# U4BNV1_Schematic.net
KiCad netlist of a schematic drawn in Altium Designer
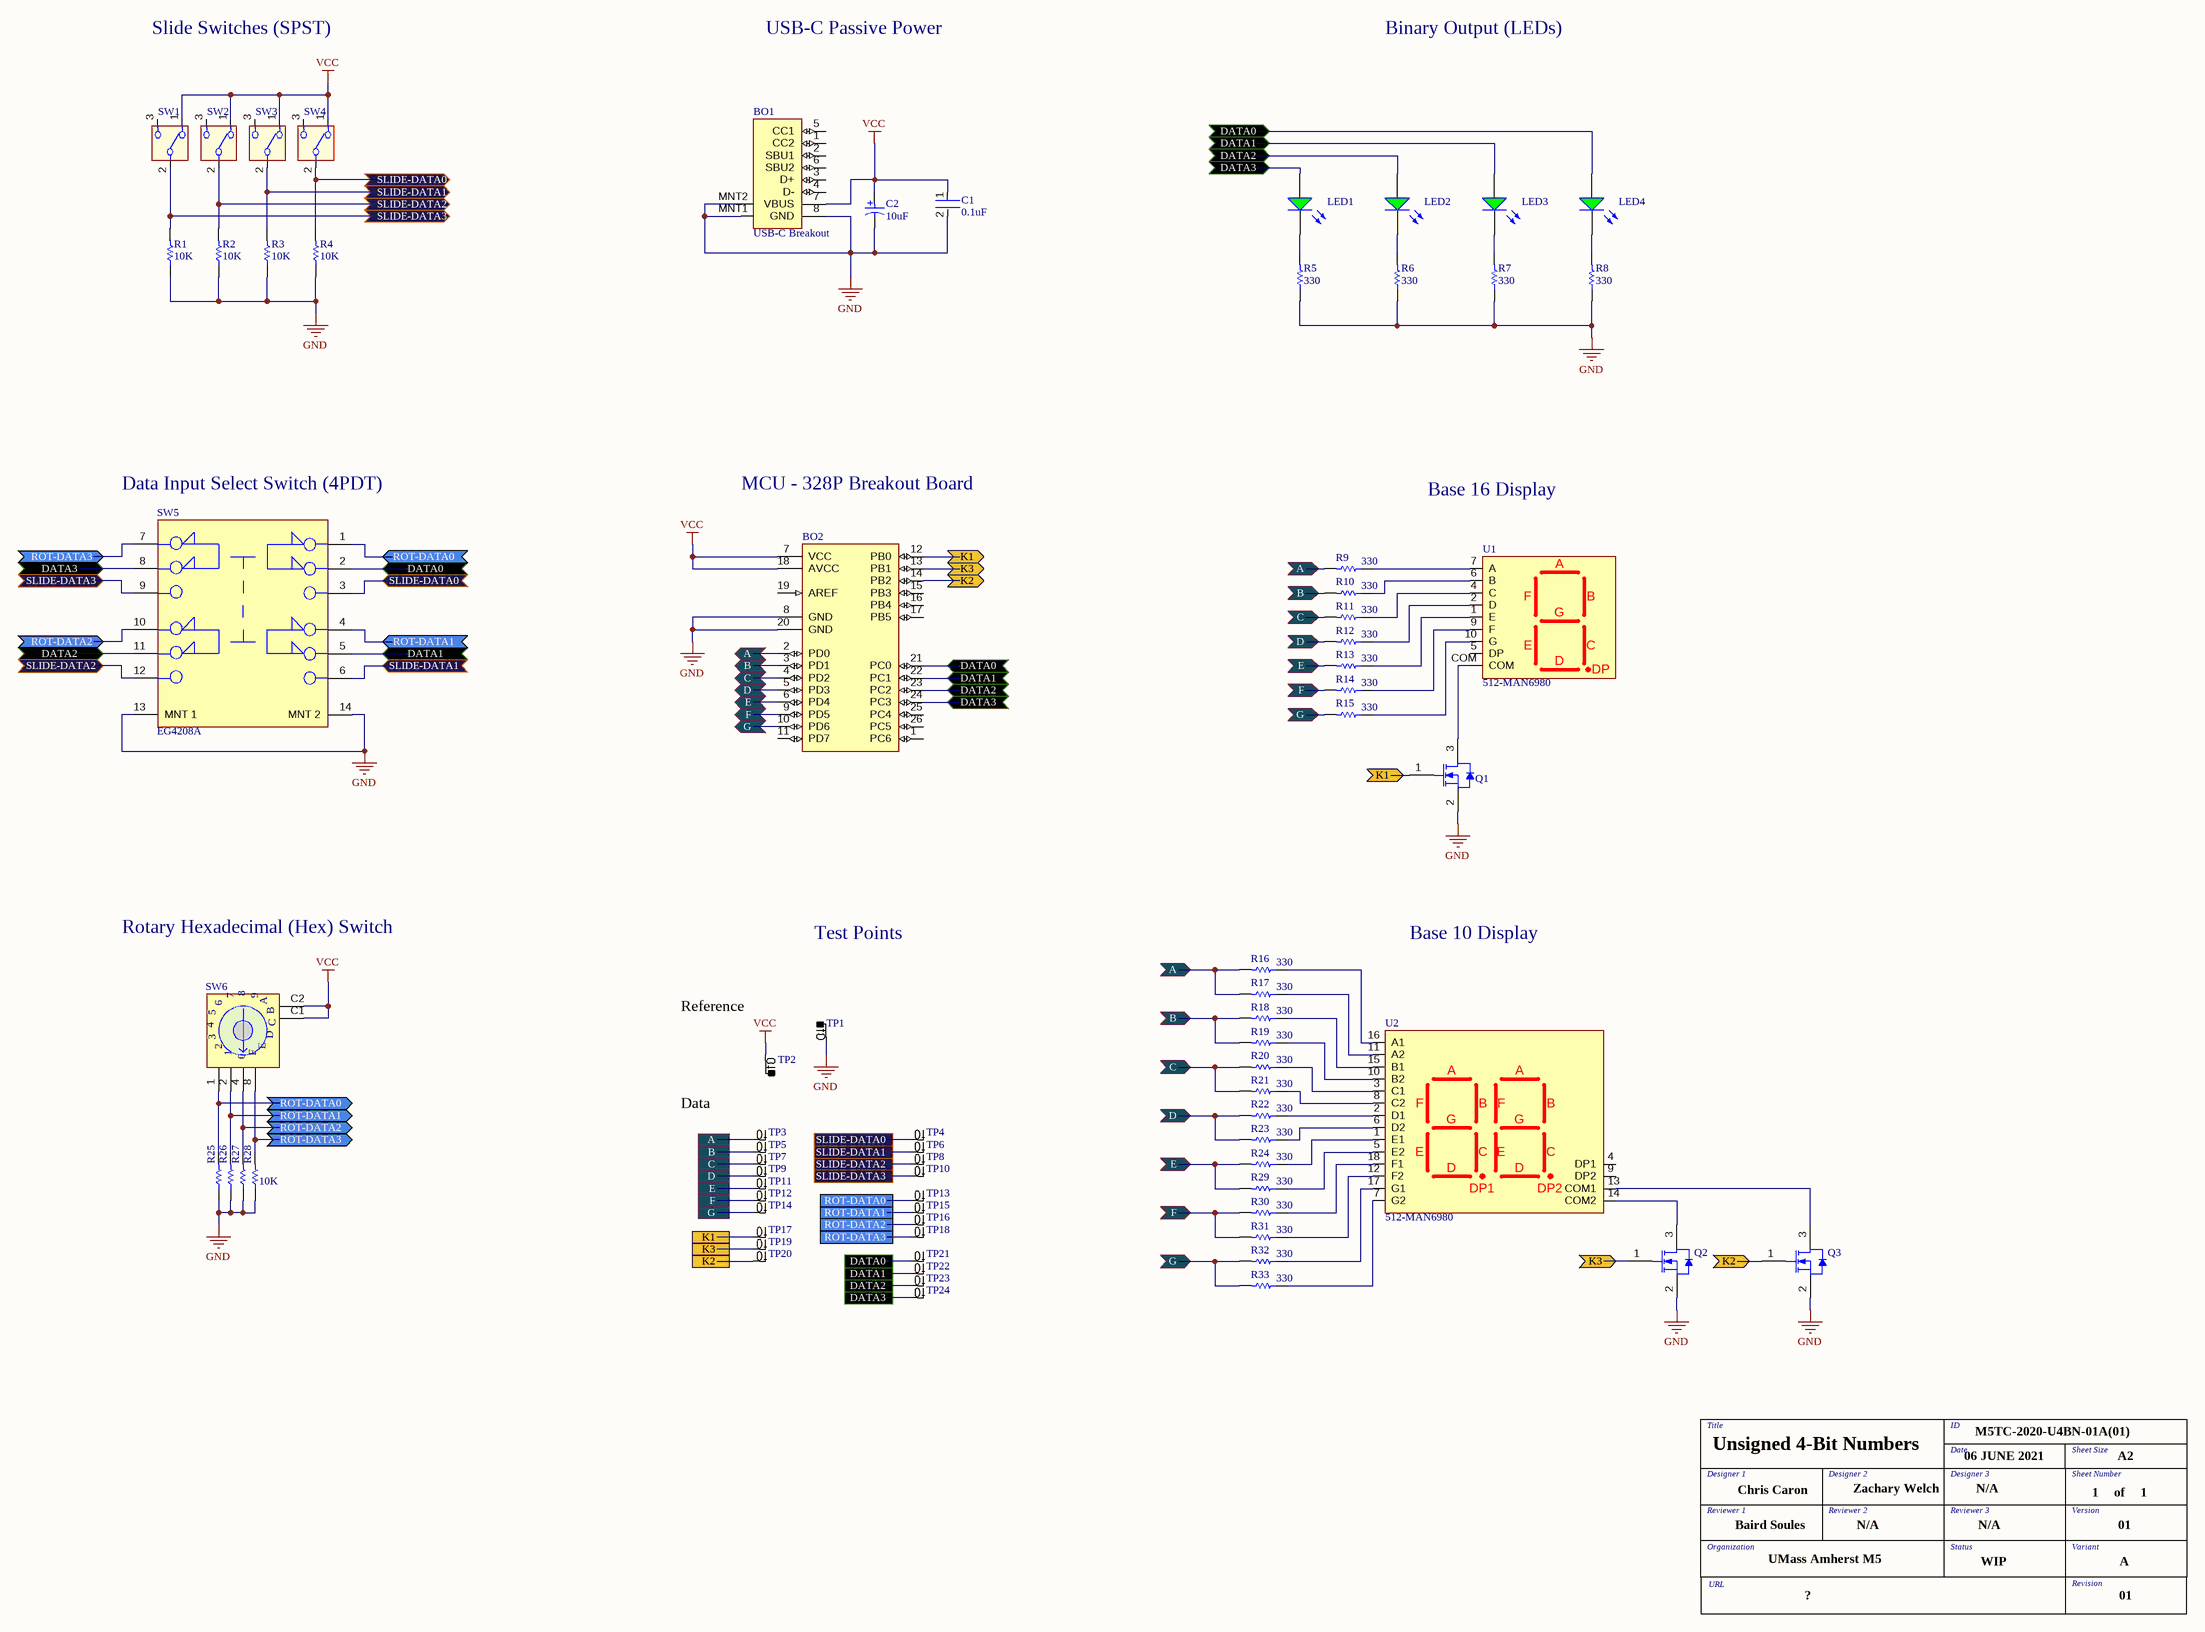
[diagram p0: U4BNV1 Schematic.SchDoc]

(export (version "E")
  (design (tool "Eeschema 10.0.6"))
  (components
    (comp (ref "BO1")
      (value "USB-C Breakout")
      (footprint "USB-C Breakout")
      (libsource (lib "U4BNV1 SchLib") (part "USB-C Breakout"))
    )
    (comp (ref "BO2")
      (value "~")
      (footprint "328P-BOB")
      (description "Custom Breakout Board for 328P-PU")
      (libsource (lib "Master Schematic Library") (part "328P-BOB"))
    )
    (comp (ref "C1")
      (value "0.1uF")
      (footprint "FP-C0603-CJ-MFG")
      (description "CAP CER 0.1UF 50V X7R 0603")
      (fields (field (name "MANUFACTURER PART NUMBER") "C0603X104K5RACTU") (field (name "VOLTAGE") "50V"))
      (libsource (lib "Altium Content Vault") (part "11868f565c42a9108669ba33697ecf6"))
    )
    (comp (ref "C2")
      (value "10uF")
      (footprint "KEMT-A-3216-18-2_M")
      (description "Capacitor, Tantalum, 10 uF, +/- 10%, 10 V, -55 to 125 degC, 2-Pin SMD (1206), RoHS, Tape and Reel")
      (fields (field (name "TOLERANCE") "±10%") (field (name "MANUFACTURER") "Kemet"))
      (libsource (lib "Altium Content Vault") (part "CAP-P-2"))
    )
    (comp (ref "LED1")
      (value "HLMP-4740")
      (footprint "AVAG-HLMP-4740")
      (description "T-1 3/4 (5 mm) Low Current LED Lamp, Green, 1.9 V, -20 to 100 degC, 2-Pin THD, RoHS, Bulk")
      (fields (field (name "MANUFACTURER") "AvagoTechnologies"))
      (libsource (lib "Altium Content Vault") (part "LED-GREEN-AK-2"))
    )
    (comp (ref "LED2")
      (value "HLMP-4740")
      (footprint "AVAG-HLMP-4740")
      (description "T-1 3/4 (5 mm) Low Current LED Lamp, Green, 1.9 V, -20 to 100 degC, 2-Pin THD, RoHS, Bulk")
      (fields (field (name "MANUFACTURER") "AvagoTechnologies"))
      (libsource (lib "Altium Content Vault") (part "LED-GREEN-AK-2"))
    )
    (comp (ref "LED3")
      (value "HLMP-4740")
      (footprint "AVAG-HLMP-4740")
      (description "T-1 3/4 (5 mm) Low Current LED Lamp, Green, 1.9 V, -20 to 100 degC, 2-Pin THD, RoHS, Bulk")
      (fields (field (name "MANUFACTURER") "AvagoTechnologies"))
      (libsource (lib "Altium Content Vault") (part "LED-GREEN-AK-2"))
    )
    (comp (ref "LED4")
      (value "HLMP-4740")
      (footprint "AVAG-HLMP-4740")
      (description "T-1 3/4 (5 mm) Low Current LED Lamp, Green, 1.9 V, -20 to 100 degC, 2-Pin THD, RoHS, Bulk")
      (fields (field (name "MANUFACTURER") "AvagoTechnologies"))
      (libsource (lib "Altium Content Vault") (part "LED-GREEN-AK-2"))
    )
    (comp (ref "Q1")
      (value "FDN337N")
      (footprint "FAIR-SSOT3L-3_V")
      (fields (field (name "MANUFACTURER") "Fairchild Semiconductor"))
      (libsource (lib "Altium Content Vault") (part "NEMOS-GSD-3"))
    )
    (comp (ref "Q2")
      (value "FDN337N")
      (footprint "FAIR-SSOT3L-3_V")
      (fields (field (name "MANUFACTURER") "Fairchild Semiconductor"))
      (libsource (lib "Altium Content Vault") (part "NEMOS-GSD-3"))
    )
    (comp (ref "Q3")
      (value "FDN337N")
      (footprint "FAIR-SSOT3L-3_V")
      (fields (field (name "MANUFACTURER") "Fairchild Semiconductor"))
      (libsource (lib "Altium Content Vault") (part "NEMOS-GSD-3"))
    )
    (comp (ref "R1")
      (value "10K")
      (footprint "RESC1608X55X30LL10T20_B")
      (description "Chip Resistor, 10 KOhm, +/- 1%, 0.1 W, -55 to 125 degC, 0603 (1608 Metric), RoHS, Tape and Reel")
      (fields (field (name "MANUFACTURER") "TE Connectivity") (field (name "TOLERANCE") "1%"))
      (libsource (lib "Altium Content Vault") (part "RES-2"))
    )
    (comp (ref "R2")
      (value "10K")
      (footprint "RESC1608X55X30LL10T20_B")
      (description "Chip Resistor, 10 KOhm, +/- 1%, 0.1 W, -55 to 125 degC, 0603 (1608 Metric), RoHS, Tape and Reel")
      (fields (field (name "MANUFACTURER") "TE Connectivity") (field (name "TOLERANCE") "1%"))
      (libsource (lib "Altium Content Vault") (part "RES-2"))
    )
    (comp (ref "R3")
      (value "10K")
      (footprint "RESC1608X55X30LL10T20_B")
      (description "Chip Resistor, 10 KOhm, +/- 1%, 0.1 W, -55 to 125 degC, 0603 (1608 Metric), RoHS, Tape and Reel")
      (fields (field (name "MANUFACTURER") "TE Connectivity") (field (name "TOLERANCE") "1%"))
      (libsource (lib "Altium Content Vault") (part "RES-2"))
    )
    (comp (ref "R4")
      (value "10K")
      (footprint "RESC1608X55X30LL10T20_B")
      (description "Chip Resistor, 10 KOhm, +/- 1%, 0.1 W, -55 to 125 degC, 0603 (1608 Metric), RoHS, Tape and Reel")
      (fields (field (name "MANUFACTURER") "TE Connectivity") (field (name "TOLERANCE") "1%"))
      (libsource (lib "Altium Content Vault") (part "RES-2"))
    )
    (comp (ref "R5")
      (value "330")
      (footprint "RESC1608X55X25NL10T15")
      (description "Chip Resistor, 330 Ohm, +/- 1%, 0.1 W, -55 to 155 degC, 0603 (1608 Metric), RoHS, Tape and Reel")
      (fields (field (name "TOLERANCE") "10%"))
      (libsource (lib "Altium Content Vault") (part "RES-2"))
    )
    (comp (ref "R6")
      (value "330")
      (footprint "RESC1608X55X25NL10T15")
      (description "Chip Resistor, 330 Ohm, +/- 1%, 0.1 W, -55 to 155 degC, 0603 (1608 Metric), RoHS, Tape and Reel")
      (fields (field (name "TOLERANCE") "10%"))
      (libsource (lib "Altium Content Vault") (part "RES-2"))
    )
    (comp (ref "R7")
      (value "330")
      (footprint "RESC1608X55X25NL10T15")
      (description "Chip Resistor, 330 Ohm, +/- 1%, 0.1 W, -55 to 155 degC, 0603 (1608 Metric), RoHS, Tape and Reel")
      (fields (field (name "TOLERANCE") "10%"))
      (libsource (lib "Altium Content Vault") (part "RES-2"))
    )
    (comp (ref "R8")
      (value "330")
      (footprint "RESC1608X55X25NL10T15")
      (description "Chip Resistor, 330 Ohm, +/- 1%, 0.1 W, -55 to 155 degC, 0603 (1608 Metric), RoHS, Tape and Reel")
      (fields (field (name "TOLERANCE") "10%"))
      (libsource (lib "Altium Content Vault") (part "RES-2"))
    )
    (comp (ref "R9")
      (value "330")
      (footprint "RESC1608X55X25NL10T15")
      (description "Chip Resistor, 330 Ohm, +/- 1%, 0.1 W, -55 to 155 degC, 0603 (1608 Metric), RoHS, Tape and Reel")
      (fields (field (name "TOLERANCE") "10%"))
      (libsource (lib "Altium Content Vault") (part "RES-2"))
    )
    (comp (ref "R10")
      (value "330")
      (footprint "RESC1608X55X25NL10T15")
      (description "Chip Resistor, 330 Ohm, +/- 1%, 0.1 W, -55 to 155 degC, 0603 (1608 Metric), RoHS, Tape and Reel")
      (fields (field (name "TOLERANCE") "10%"))
      (libsource (lib "Altium Content Vault") (part "RES-2"))
    )
    (comp (ref "R11")
      (value "330")
      (footprint "RESC1608X55X25NL10T15")
      (description "Chip Resistor, 330 Ohm, +/- 1%, 0.1 W, -55 to 155 degC, 0603 (1608 Metric), RoHS, Tape and Reel")
      (fields (field (name "TOLERANCE") "10%"))
      (libsource (lib "Altium Content Vault") (part "RES-2"))
    )
    (comp (ref "R12")
      (value "330")
      (footprint "RESC1608X55X25NL10T15")
      (description "Chip Resistor, 330 Ohm, +/- 1%, 0.1 W, -55 to 155 degC, 0603 (1608 Metric), RoHS, Tape and Reel")
      (fields (field (name "TOLERANCE") "10%"))
      (libsource (lib "Altium Content Vault") (part "RES-2"))
    )
    (comp (ref "R13")
      (value "330")
      (footprint "RESC1608X55X25NL10T15")
      (description "Chip Resistor, 330 Ohm, +/- 1%, 0.1 W, -55 to 155 degC, 0603 (1608 Metric), RoHS, Tape and Reel")
      (fields (field (name "TOLERANCE") "10%"))
      (libsource (lib "Altium Content Vault") (part "RES-2"))
    )
    (comp (ref "R14")
      (value "330")
      (footprint "RESC1608X55X25NL10T15")
      (description "Chip Resistor, 330 Ohm, +/- 1%, 0.1 W, -55 to 155 degC, 0603 (1608 Metric), RoHS, Tape and Reel")
      (fields (field (name "TOLERANCE") "10%"))
      (libsource (lib "Altium Content Vault") (part "RES-2"))
    )
    (comp (ref "R15")
      (value "330")
      (footprint "RESC1608X55X25NL10T15")
      (description "Chip Resistor, 330 Ohm, +/- 1%, 0.1 W, -55 to 155 degC, 0603 (1608 Metric), RoHS, Tape and Reel")
      (fields (field (name "TOLERANCE") "10%"))
      (libsource (lib "Altium Content Vault") (part "RES-2"))
    )
    (comp (ref "R16")
      (value "330")
      (footprint "RESC1608X55X25NL10T15")
      (description "Chip Resistor, 330 Ohm, +/- 1%, 0.1 W, -55 to 155 degC, 0603 (1608 Metric), RoHS, Tape and Reel")
      (fields (field (name "TOLERANCE") "10%"))
      (libsource (lib "Altium Content Vault") (part "RES-2"))
    )
    (comp (ref "R17")
      (value "330")
      (footprint "RESC1608X55X25NL10T15")
      (description "Chip Resistor, 330 Ohm, +/- 1%, 0.1 W, -55 to 155 degC, 0603 (1608 Metric), RoHS, Tape and Reel")
      (fields (field (name "TOLERANCE") "10%"))
      (libsource (lib "Altium Content Vault") (part "RES-2"))
    )
    (comp (ref "R18")
      (value "330")
      (footprint "RESC1608X55X25NL10T15")
      (description "Chip Resistor, 330 Ohm, +/- 1%, 0.1 W, -55 to 155 degC, 0603 (1608 Metric), RoHS, Tape and Reel")
      (fields (field (name "TOLERANCE") "10%"))
      (libsource (lib "Altium Content Vault") (part "RES-2"))
    )
    (comp (ref "R19")
      (value "330")
      (footprint "RESC1608X55X25NL10T15")
      (description "Chip Resistor, 330 Ohm, +/- 1%, 0.1 W, -55 to 155 degC, 0603 (1608 Metric), RoHS, Tape and Reel")
      (fields (field (name "TOLERANCE") "10%"))
      (libsource (lib "Altium Content Vault") (part "RES-2"))
    )
    (comp (ref "R20")
      (value "330")
      (footprint "RESC1608X55X25NL10T15")
      (description "Chip Resistor, 330 Ohm, +/- 1%, 0.1 W, -55 to 155 degC, 0603 (1608 Metric), RoHS, Tape and Reel")
      (fields (field (name "TOLERANCE") "10%"))
      (libsource (lib "Altium Content Vault") (part "RES-2"))
    )
    (comp (ref "R21")
      (value "330")
      (footprint "RESC1608X55X25NL10T15")
      (description "Chip Resistor, 330 Ohm, +/- 1%, 0.1 W, -55 to 155 degC, 0603 (1608 Metric), RoHS, Tape and Reel")
      (fields (field (name "TOLERANCE") "10%"))
      (libsource (lib "Altium Content Vault") (part "RES-2"))
    )
    (comp (ref "R22")
      (value "330")
      (footprint "RESC1608X55X25NL10T15")
      (description "Chip Resistor, 330 Ohm, +/- 1%, 0.1 W, -55 to 155 degC, 0603 (1608 Metric), RoHS, Tape and Reel")
      (fields (field (name "TOLERANCE") "10%"))
      (libsource (lib "Altium Content Vault") (part "RES-2"))
    )
    (comp (ref "R23")
      (value "330")
      (footprint "RESC1608X55X25NL10T15")
      (description "Chip Resistor, 330 Ohm, +/- 1%, 0.1 W, -55 to 155 degC, 0603 (1608 Metric), RoHS, Tape and Reel")
      (fields (field (name "TOLERANCE") "10%"))
      (libsource (lib "Altium Content Vault") (part "RES-2"))
    )
    (comp (ref "R24")
      (value "330")
      (footprint "RESC1608X55X25NL10T15")
      (description "Chip Resistor, 330 Ohm, +/- 1%, 0.1 W, -55 to 155 degC, 0603 (1608 Metric), RoHS, Tape and Reel")
      (fields (field (name "TOLERANCE") "10%"))
      (libsource (lib "Altium Content Vault") (part "RES-2"))
    )
    (comp (ref "R25")
      (value "10K")
      (footprint "RESC1609X55X30ML10T20")
      (description "Res Thin Film 0603 10K Ohm 0.1% 1/10W ±25ppm/°C Molded SMD SMD Paper T/R")
      (fields (field (name "PART NUMBER") "TNPW060310K0BETA") (field (name "MANUFACTURER") "Vishay Dale"))
      (libsource (lib "Altium Content Vault") (part "RES"))
    )
    (comp (ref "R26")
      (value "10K")
      (footprint "RESC1609X55X30ML10T20")
      (description "Res Thin Film 0603 10K Ohm 0.1% 1/10W ±25ppm/°C Molded SMD SMD Paper T/R")
      (fields (field (name "PART NUMBER") "TNPW060310K0BETA") (field (name "MANUFACTURER") "Vishay Dale"))
      (libsource (lib "Altium Content Vault") (part "RES"))
    )
    (comp (ref "R27")
      (value "10K")
      (footprint "RESC1609X55X30ML10T20")
      (description "Res Thin Film 0603 10K Ohm 0.1% 1/10W ±25ppm/°C Molded SMD SMD Paper T/R")
      (fields (field (name "PART NUMBER") "TNPW060310K0BETA") (field (name "MANUFACTURER") "Vishay Dale"))
      (libsource (lib "Altium Content Vault") (part "RES"))
    )
    (comp (ref "R28")
      (value "10K")
      (footprint "RESC1609X55X30ML10T20")
      (description "Res Thin Film 0603 10K Ohm 0.1% 1/10W ±25ppm/°C Molded SMD SMD Paper T/R")
      (fields (field (name "PART NUMBER") "TNPW060310K0BETA") (field (name "MANUFACTURER") "Vishay Dale"))
      (libsource (lib "Altium Content Vault") (part "RES"))
    )
    (comp (ref "R29")
      (value "330")
      (footprint "RESC1608X55X25NL10T15")
      (description "Chip Resistor, 330 Ohm, +/- 1%, 0.1 W, -55 to 155 degC, 0603 (1608 Metric), RoHS, Tape and Reel")
      (fields (field (name "TOLERANCE") "10%"))
      (libsource (lib "Altium Content Vault") (part "RES-2"))
    )
    (comp (ref "R30")
      (value "330")
      (footprint "RESC1608X55X25NL10T15")
      (description "Chip Resistor, 330 Ohm, +/- 1%, 0.1 W, -55 to 155 degC, 0603 (1608 Metric), RoHS, Tape and Reel")
      (fields (field (name "TOLERANCE") "10%"))
      (libsource (lib "Altium Content Vault") (part "RES-2"))
    )
    (comp (ref "R31")
      (value "330")
      (footprint "RESC1608X55X25NL10T15")
      (description "Chip Resistor, 330 Ohm, +/- 1%, 0.1 W, -55 to 155 degC, 0603 (1608 Metric), RoHS, Tape and Reel")
      (fields (field (name "TOLERANCE") "10%"))
      (libsource (lib "Altium Content Vault") (part "RES-2"))
    )
    (comp (ref "R32")
      (value "330")
      (footprint "RESC1608X55X25NL10T15")
      (description "Chip Resistor, 330 Ohm, +/- 1%, 0.1 W, -55 to 155 degC, 0603 (1608 Metric), RoHS, Tape and Reel")
      (fields (field (name "TOLERANCE") "10%"))
      (libsource (lib "Altium Content Vault") (part "RES-2"))
    )
    (comp (ref "R33")
      (value "330")
      (footprint "RESC1608X55X25NL10T15")
      (description "Chip Resistor, 330 Ohm, +/- 1%, 0.1 W, -55 to 155 degC, 0603 (1608 Metric), RoHS, Tape and Reel")
      (fields (field (name "TOLERANCE") "10%"))
      (libsource (lib "Altium Content Vault") (part "RES-2"))
    )
    (comp (ref "SW1")
      (value "SPDT SLIDE 48ASSP1S1M2RBT")
      (footprint "SPDT SLIDE 48ASSP1S1M2RBT")
      (description "SWITCH SLIDE SPDT 0.4VA 20V")
      (libsource (lib "Master Schematic Library") (part "SPDT SLIDE 48ASSP1S1M2RBT"))
    )
    (comp (ref "SW2")
      (value "SPDT SLIDE 48ASSP1S1M2RBT")
      (footprint "SPDT SLIDE 48ASSP1S1M2RBT")
      (description "SWITCH SLIDE SPDT 0.4VA 20V")
      (libsource (lib "Master Schematic Library") (part "SPDT SLIDE 48ASSP1S1M2RBT"))
    )
    (comp (ref "SW3")
      (value "SPDT SLIDE 48ASSP1S1M2RBT")
      (footprint "SPDT SLIDE 48ASSP1S1M2RBT")
      (description "SWITCH SLIDE SPDT 0.4VA 20V")
      (libsource (lib "Master Schematic Library") (part "SPDT SLIDE 48ASSP1S1M2RBT"))
    )
    (comp (ref "SW4")
      (value "SPDT SLIDE 48ASSP1S1M2RBT")
      (footprint "SPDT SLIDE 48ASSP1S1M2RBT")
      (description "SWITCH SLIDE SPDT 0.4VA 20V")
      (libsource (lib "Master Schematic Library") (part "SPDT SLIDE 48ASSP1S1M2RBT"))
    )
    (comp (ref "SW5")
      (value "EG4208A")
      (footprint "FP-EG4208A-MFG")
      (description "SWITCH SLIDE 4PDT 200MA 30V")
      (fields
        (field (name "MANUFACTURER") "E-Switch")
        (field (name "OCTOPART") "https://octopart.com/eg4208a-e-switch-1221143")
      )
      (libsource (lib "Altium Content Vault") (part "584696742aae54c36ba8ba511d23bcf"))
    )
    (comp (ref "SW6")
      (value "428521420916")
      (footprint "428521420916")
      (description "WS-ROSV SMD Rotary Switch 10x10 mm")
      (fields (field (name "MANUFACTURER") "Wuerth Elektronik"))
      (libsource (lib "Altium Content Vault") (part "WS-ROTARY-SW-6_16P"))
    )
    (comp (ref "Tb1") (value "Title Block") (libsource (lib "Master Schematic Library") (part "Title Block")))
    (comp (ref "TP1")
      (value "Loop post and pad test point")
      (footprint "TEST POINT (LOOP/POST/PAD)")
      (description "Requires 1 Keystone Electronics PC Test Point Multipurpose (see 5011 for example)")
      (libsource (lib "Master Library") (part "Test Point (Loop/Post/Pad)"))
    )
    (comp (ref "TP2")
      (value "Loop post and pad test point")
      (footprint "TEST POINT (LOOP/POST/PAD)")
      (description "Requires 1 Keystone Electronics PC Test Point Multipurpose (see 5011 for example)")
      (libsource (lib "Master Library") (part "Test Point (Loop/Post/Pad)"))
    )
    (comp (ref "TP3")
      (value "Loop and post test point")
      (footprint "TEST POINT (LOOP/POST)")
      (description "Requires 1 Keystone Electronics PC Test Point Multipurpose (see 5011 for example)")
      (libsource (lib "Master Library") (part "Test Point (Loop/Post)"))
    )
    (comp (ref "TP4")
      (value "Loop and post test point")
      (footprint "TEST POINT (LOOP/POST)")
      (description "Requires 1 Keystone Electronics PC Test Point Multipurpose (see 5011 for example)")
      (libsource (lib "Master Library") (part "Test Point (Loop/Post)"))
    )
    (comp (ref "TP5")
      (value "Loop and post test point")
      (footprint "TEST POINT (LOOP/POST)")
      (description "Requires 1 Keystone Electronics PC Test Point Multipurpose (see 5011 for example)")
      (libsource (lib "Master Library") (part "Test Point (Loop/Post)"))
    )
    (comp (ref "TP6")
      (value "Loop and post test point")
      (footprint "TEST POINT (LOOP/POST)")
      (description "Requires 1 Keystone Electronics PC Test Point Multipurpose (see 5011 for example)")
      (libsource (lib "Master Library") (part "Test Point (Loop/Post)"))
    )
    (comp (ref "TP7")
      (value "Loop and post test point")
      (footprint "TEST POINT (LOOP/POST)")
      (description "Requires 1 Keystone Electronics PC Test Point Multipurpose (see 5011 for example)")
      (libsource (lib "Master Library") (part "Test Point (Loop/Post)"))
    )
    (comp (ref "TP8")
      (value "Loop and post test point")
      (footprint "TEST POINT (LOOP/POST)")
      (description "Requires 1 Keystone Electronics PC Test Point Multipurpose (see 5011 for example)")
      (libsource (lib "Master Library") (part "Test Point (Loop/Post)"))
    )
    (comp (ref "TP9")
      (value "Loop and post test point")
      (footprint "TEST POINT (LOOP/POST)")
      (description "Requires 1 Keystone Electronics PC Test Point Multipurpose (see 5011 for example)")
      (libsource (lib "Master Library") (part "Test Point (Loop/Post)"))
    )
    (comp (ref "TP10")
      (value "Loop and post test point")
      (footprint "TEST POINT (LOOP/POST)")
      (description "Requires 1 Keystone Electronics PC Test Point Multipurpose (see 5011 for example)")
      (libsource (lib "Master Library") (part "Test Point (Loop/Post)"))
    )
    (comp (ref "TP11")
      (value "Loop and post test point")
      (footprint "TEST POINT (LOOP/POST)")
      (description "Requires 1 Keystone Electronics PC Test Point Multipurpose (see 5011 for example)")
      (libsource (lib "Master Library") (part "Test Point (Loop/Post)"))
    )
    (comp (ref "TP12")
      (value "Loop and post test point")
      (footprint "TEST POINT (LOOP/POST)")
      (description "Requires 1 Keystone Electronics PC Test Point Multipurpose (see 5011 for example)")
      (libsource (lib "Master Library") (part "Test Point (Loop/Post)"))
    )
    (comp (ref "TP13")
      (value "Loop and post test point")
      (footprint "TEST POINT (LOOP/POST)")
      (description "Requires 1 Keystone Electronics PC Test Point Multipurpose (see 5011 for example)")
      (libsource (lib "Master Library") (part "Test Point (Loop/Post)"))
    )
    (comp (ref "TP14")
      (value "Loop and post test point")
      (footprint "TEST POINT (LOOP/POST)")
      (description "Requires 1 Keystone Electronics PC Test Point Multipurpose (see 5011 for example)")
      (libsource (lib "Master Library") (part "Test Point (Loop/Post)"))
    )
    (comp (ref "TP15")
      (value "Loop and post test point")
      (footprint "TEST POINT (LOOP/POST)")
      (description "Requires 1 Keystone Electronics PC Test Point Multipurpose (see 5011 for example)")
      (libsource (lib "Master Library") (part "Test Point (Loop/Post)"))
    )
    (comp (ref "TP16")
      (value "Loop and post test point")
      (footprint "TEST POINT (LOOP/POST)")
      (description "Requires 1 Keystone Electronics PC Test Point Multipurpose (see 5011 for example)")
      (libsource (lib "Master Library") (part "Test Point (Loop/Post)"))
    )
    (comp (ref "TP17")
      (value "Loop and post test point")
      (footprint "TEST POINT (LOOP/POST)")
      (description "Requires 1 Keystone Electronics PC Test Point Multipurpose (see 5011 for example)")
      (libsource (lib "Master Library") (part "Test Point (Loop/Post)"))
    )
    (comp (ref "TP18")
      (value "Loop and post test point")
      (footprint "TEST POINT (LOOP/POST)")
      (description "Requires 1 Keystone Electronics PC Test Point Multipurpose (see 5011 for example)")
      (libsource (lib "Master Library") (part "Test Point (Loop/Post)"))
    )
    (comp (ref "TP19")
      (value "Loop and post test point")
      (footprint "TEST POINT (LOOP/POST)")
      (description "Requires 1 Keystone Electronics PC Test Point Multipurpose (see 5011 for example)")
      (libsource (lib "Master Library") (part "Test Point (Loop/Post)"))
    )
    (comp (ref "TP20")
      (value "Loop and post test point")
      (footprint "TEST POINT (LOOP/POST)")
      (description "Requires 1 Keystone Electronics PC Test Point Multipurpose (see 5011 for example)")
      (libsource (lib "Master Library") (part "Test Point (Loop/Post)"))
    )
    (comp (ref "TP21")
      (value "Loop and post test point")
      (footprint "TEST POINT (LOOP/POST)")
      (description "Requires 1 Keystone Electronics PC Test Point Multipurpose (see 5011 for example)")
      (libsource (lib "Master Library") (part "Test Point (Loop/Post)"))
    )
    (comp (ref "TP22")
      (value "Loop and post test point")
      (footprint "TEST POINT (LOOP/POST)")
      (description "Requires 1 Keystone Electronics PC Test Point Multipurpose (see 5011 for example)")
      (libsource (lib "Master Library") (part "Test Point (Loop/Post)"))
    )
    (comp (ref "TP23")
      (value "Loop and post test point")
      (footprint "TEST POINT (LOOP/POST)")
      (description "Requires 1 Keystone Electronics PC Test Point Multipurpose (see 5011 for example)")
      (libsource (lib "Master Library") (part "Test Point (Loop/Post)"))
    )
    (comp (ref "TP24")
      (value "Loop and post test point")
      (footprint "TEST POINT (LOOP/POST)")
      (description "Requires 1 Keystone Electronics PC Test Point Multipurpose (see 5011 for example)")
      (libsource (lib "Master Library") (part "Test Point (Loop/Post)"))
    )
    (comp (ref "U1")
      (value "Single Digit CC")
      (footprint "MAN6980")
      (description "MAN6980 RED SINGLE DIGIT COMMON CATHODE RT. HAND DECIMAL - FAIRCHILD SEMICONDUCTOR")
      (fields (field (name "SUPPLIER PART NUMBER 1") "512-MAN6980"))
      (libsource (lib "Master Library") (part "7 Seg 1 Digit MAN6980"))
    )
    (comp (ref "U2")
      (value "2 Digit MAN6940")
      (footprint "MAN6940")
      (description "MAN6940 RED DOUBLE DIGIT COMMON CATHODE RT. HAND DECIMAL - FAIRCHILD SEMICONDUCTOR")
      (fields (field (name "SUPPLIER PART NUMBER 1") "512-MAN6980"))
      (libsource (lib "Master Library") (part "7 Seg 2 Digit MAN6940"))
    )
  )
  (nets
    (net (code "1") (name "/A") (class "Default")
      (node (ref "BO2") (pin "2") (pinfunction "PD0_2") (pintype "bidirectional"))
      (node (ref "R16") (pin "2") (pinfunction "2_2") (pintype "passive"))
      (node (ref "R17") (pin "2") (pinfunction "2_2") (pintype "passive"))
      (node (ref "R9") (pin "2") (pinfunction "2_2") (pintype "passive"))
      (node (ref "TP3") (pin "1") (pinfunction "1_1") (pintype "passive"))
    )
    (net (code "2") (name "/B") (class "Default")
      (node (ref "BO2") (pin "3") (pinfunction "PD1_3") (pintype "bidirectional"))
      (node (ref "R10") (pin "2") (pinfunction "2_2") (pintype "passive"))
      (node (ref "R18") (pin "2") (pinfunction "2_2") (pintype "passive"))
      (node (ref "R19") (pin "2") (pinfunction "2_2") (pintype "passive"))
      (node (ref "TP5") (pin "1") (pinfunction "1_1") (pintype "passive"))
    )
    (net (code "3") (name "/C") (class "Default")
      (node (ref "BO2") (pin "4") (pinfunction "PD2_4") (pintype "bidirectional"))
      (node (ref "R11") (pin "2") (pinfunction "2_2") (pintype "passive"))
      (node (ref "R20") (pin "2") (pinfunction "2_2") (pintype "passive"))
      (node (ref "R21") (pin "2") (pinfunction "2_2") (pintype "passive"))
      (node (ref "TP7") (pin "1") (pinfunction "1_1") (pintype "passive"))
    )
    (net (code "4") (name "/D") (class "Default")
      (node (ref "BO2") (pin "5") (pinfunction "PD3_5") (pintype "bidirectional"))
      (node (ref "R12") (pin "2") (pinfunction "2_2") (pintype "passive"))
      (node (ref "R22") (pin "2") (pinfunction "2_2") (pintype "passive"))
      (node (ref "R23") (pin "2") (pinfunction "2_2") (pintype "passive"))
      (node (ref "TP9") (pin "1") (pinfunction "1_1") (pintype "passive"))
    )
    (net (code "5") (name "/DATA0") (class "Default")
      (node (ref "BO2") (pin "21") (pinfunction "PC0_21") (pintype "bidirectional"))
      (node (ref "LED4") (pin "1") (pinfunction "A_1") (pintype "passive"))
      (node (ref "SW5") (pin "2") (pinfunction "2_2") (pintype "passive"))
      (node (ref "TP21") (pin "1") (pinfunction "1_1") (pintype "passive"))
    )
    (net (code "6") (name "/DATA1") (class "Default")
      (node (ref "BO2") (pin "22") (pinfunction "PC1_22") (pintype "bidirectional"))
      (node (ref "LED3") (pin "1") (pinfunction "A_1") (pintype "passive"))
      (node (ref "SW5") (pin "5") (pinfunction "5_5") (pintype "passive"))
      (node (ref "TP22") (pin "1") (pinfunction "1_1") (pintype "passive"))
    )
    (net (code "7") (name "/DATA2") (class "Default")
      (node (ref "BO2") (pin "23") (pinfunction "PC2_23") (pintype "bidirectional"))
      (node (ref "LED2") (pin "1") (pinfunction "A_1") (pintype "passive"))
      (node (ref "SW5") (pin "11") (pinfunction "11_11") (pintype "passive"))
      (node (ref "TP23") (pin "1") (pinfunction "1_1") (pintype "passive"))
    )
    (net (code "8") (name "/DATA3") (class "Default")
      (node (ref "BO2") (pin "24") (pinfunction "PC3_24") (pintype "bidirectional"))
      (node (ref "LED1") (pin "1") (pinfunction "A_1") (pintype "passive"))
      (node (ref "SW5") (pin "8") (pinfunction "8_8") (pintype "passive"))
      (node (ref "TP24") (pin "1") (pinfunction "1_1") (pintype "passive"))
    )
    (net (code "9") (name "/E") (class "Default")
      (node (ref "BO2") (pin "6") (pinfunction "PD4_6") (pintype "bidirectional"))
      (node (ref "R13") (pin "2") (pinfunction "2_2") (pintype "passive"))
      (node (ref "R24") (pin "2") (pinfunction "2_2") (pintype "passive"))
      (node (ref "R29") (pin "2") (pinfunction "2_2") (pintype "passive"))
      (node (ref "TP11") (pin "1") (pinfunction "1_1") (pintype "passive"))
    )
    (net (code "10") (name "/F") (class "Default")
      (node (ref "BO2") (pin "9") (pinfunction "PD5_9") (pintype "bidirectional"))
      (node (ref "R14") (pin "2") (pinfunction "2_2") (pintype "passive"))
      (node (ref "R30") (pin "2") (pinfunction "2_2") (pintype "passive"))
      (node (ref "R31") (pin "2") (pinfunction "2_2") (pintype "passive"))
      (node (ref "TP12") (pin "1") (pinfunction "1_1") (pintype "passive"))
    )
    (net (code "11") (name "/G") (class "Default")
      (node (ref "BO2") (pin "10") (pinfunction "PD6_10") (pintype "bidirectional"))
      (node (ref "R15") (pin "2") (pinfunction "2_2") (pintype "passive"))
      (node (ref "R32") (pin "2") (pinfunction "2_2") (pintype "passive"))
      (node (ref "R33") (pin "2") (pinfunction "2_2") (pintype "passive"))
      (node (ref "TP14") (pin "1") (pinfunction "1_1") (pintype "passive"))
    )
    (net (code "12") (name "/K1") (class "Default")
      (node (ref "BO2") (pin "12") (pinfunction "PB0_12") (pintype "bidirectional"))
      (node (ref "Q1") (pin "1") (pinfunction "G_1") (pintype "passive"))
      (node (ref "TP17") (pin "1") (pinfunction "1_1") (pintype "passive"))
    )
    (net (code "13") (name "/K2") (class "Default")
      (node (ref "BO2") (pin "14") (pinfunction "PB2_14") (pintype "bidirectional"))
      (node (ref "Q3") (pin "1") (pinfunction "G_1") (pintype "passive"))
      (node (ref "TP20") (pin "1") (pinfunction "1_1") (pintype "passive"))
    )
    (net (code "14") (name "/K3") (class "Default")
      (node (ref "BO2") (pin "13") (pinfunction "PB1_13") (pintype "bidirectional"))
      (node (ref "Q2") (pin "1") (pinfunction "G_1") (pintype "passive"))
      (node (ref "TP19") (pin "1") (pinfunction "1_1") (pintype "passive"))
    )
    (net (code "15") (name "/ROT-DATA0") (class "Default")
      (node (ref "R25") (pin "2") (pinfunction "2_2") (pintype "passive"))
      (node (ref "SW5") (pin "1") (pinfunction "1_1") (pintype "passive"))
      (node (ref "SW6") (pin "1") (pinfunction "1_1") (pintype "passive"))
      (node (ref "TP13") (pin "1") (pinfunction "1_1") (pintype "passive"))
    )
    (net (code "16") (name "/ROT-DATA1") (class "Default")
      (node (ref "R26") (pin "2") (pinfunction "2_2") (pintype "passive"))
      (node (ref "SW5") (pin "4") (pinfunction "4_4") (pintype "passive"))
      (node (ref "SW6") (pin "2") (pinfunction "2_2") (pintype "passive"))
      (node (ref "TP15") (pin "1") (pinfunction "1_1") (pintype "passive"))
    )
    (net (code "17") (name "/ROT-DATA2") (class "Default")
      (node (ref "R27") (pin "2") (pinfunction "2_2") (pintype "passive"))
      (node (ref "SW5") (pin "10") (pinfunction "10_10") (pintype "passive"))
      (node (ref "SW6") (pin "4") (pinfunction "4_4") (pintype "passive"))
      (node (ref "TP16") (pin "1") (pinfunction "1_1") (pintype "passive"))
    )
    (net (code "18") (name "/ROT-DATA3") (class "Default")
      (node (ref "R28") (pin "2") (pinfunction "2_2") (pintype "passive"))
      (node (ref "SW5") (pin "7") (pinfunction "7_7") (pintype "passive"))
      (node (ref "SW6") (pin "8") (pinfunction "8_8") (pintype "passive"))
      (node (ref "TP18") (pin "1") (pinfunction "1_1") (pintype "passive"))
    )
    (net (code "19") (name "/SLIDE-DATA0") (class "Default")
      (node (ref "R4") (pin "2") (pinfunction "2_2") (pintype "passive"))
      (node (ref "SW4") (pin "2") (pinfunction "2_2") (pintype "passive"))
      (node (ref "SW5") (pin "3") (pinfunction "3_3") (pintype "passive"))
      (node (ref "TP4") (pin "1") (pinfunction "1_1") (pintype "passive"))
    )
    (net (code "20") (name "/SLIDE-DATA1") (class "Default")
      (node (ref "R3") (pin "2") (pinfunction "2_2") (pintype "passive"))
      (node (ref "SW3") (pin "2") (pinfunction "2_2") (pintype "passive"))
      (node (ref "SW5") (pin "6") (pinfunction "6_6") (pintype "passive"))
      (node (ref "TP6") (pin "1") (pinfunction "1_1") (pintype "passive"))
    )
    (net (code "21") (name "/SLIDE-DATA2") (class "Default")
      (node (ref "R2") (pin "2") (pinfunction "2_2") (pintype "passive"))
      (node (ref "SW2") (pin "2") (pinfunction "2_2") (pintype "passive"))
      (node (ref "SW5") (pin "12") (pinfunction "12_12") (pintype "passive"))
      (node (ref "TP8") (pin "1") (pinfunction "1_1") (pintype "passive"))
    )
    (net (code "22") (name "/SLIDE-DATA3") (class "Default")
      (node (ref "R1") (pin "2") (pinfunction "2_2") (pintype "passive"))
      (node (ref "SW1") (pin "2") (pinfunction "2_2") (pintype "passive"))
      (node (ref "SW5") (pin "9") (pinfunction "9_9") (pintype "passive"))
      (node (ref "TP10") (pin "1") (pinfunction "1_1") (pintype "passive"))
    )
    (net (code "23") (name "GND") (class "Default")
      (node (ref "BO1") (pin "8") (pinfunction "GND_8") (pintype "power_in"))
      (node (ref "BO1") (pin "MNT1") (pinfunction "MNT1_MNT1") (pintype "passive"))
      (node (ref "BO1") (pin "MNT2") (pinfunction "MNT2_MNT2") (pintype "passive"))
      (node (ref "BO2") (pin "20") (pinfunction "GND_20") (pintype "power_in"))
      (node (ref "BO2") (pin "8") (pinfunction "GND_8") (pintype "power_in"))
      (node (ref "C1") (pin "2") (pinfunction "2_2") (pintype "passive"))
      (node (ref "C2") (pin "2") (pinfunction "2_2") (pintype "passive"))
      (node (ref "Q1") (pin "2") (pinfunction "S_2") (pintype "passive"))
      (node (ref "Q2") (pin "2") (pinfunction "S_2") (pintype "passive"))
      (node (ref "Q3") (pin "2") (pinfunction "S_2") (pintype "passive"))
      (node (ref "R1") (pin "1") (pinfunction "1_1") (pintype "passive"))
      (node (ref "R2") (pin "1") (pinfunction "1_1") (pintype "passive"))
      (node (ref "R25") (pin "1") (pinfunction "1_1") (pintype "passive"))
      (node (ref "R26") (pin "1") (pinfunction "1_1") (pintype "passive"))
      (node (ref "R27") (pin "1") (pinfunction "1_1") (pintype "passive"))
      (node (ref "R28") (pin "1") (pinfunction "1_1") (pintype "passive"))
      (node (ref "R3") (pin "1") (pinfunction "1_1") (pintype "passive"))
      (node (ref "R4") (pin "1") (pinfunction "1_1") (pintype "passive"))
      (node (ref "R5") (pin "1") (pinfunction "1_1") (pintype "passive"))
      (node (ref "R6") (pin "1") (pinfunction "1_1") (pintype "passive"))
      (node (ref "R7") (pin "1") (pinfunction "1_1") (pintype "passive"))
      (node (ref "R8") (pin "1") (pinfunction "1_1") (pintype "passive"))
      (node (ref "SW5") (pin "13") (pinfunction "MNT_1_13") (pintype "passive"))
      (node (ref "SW5") (pin "14") (pinfunction "MNT_2_14") (pintype "passive"))
      (node (ref "TP1") (pin "1") (pinfunction "1_1") (pintype "passive"))
    )
    (net (code "24") (name "Net-(LED1-K)") (class "Default")
      (node (ref "LED1") (pin "2") (pinfunction "K_2") (pintype "passive"))
      (node (ref "R5") (pin "2") (pinfunction "2_2") (pintype "passive"))
    )
    (net (code "25") (name "Net-(LED2-K)") (class "Default")
      (node (ref "LED2") (pin "2") (pinfunction "K_2") (pintype "passive"))
      (node (ref "R6") (pin "2") (pinfunction "2_2") (pintype "passive"))
    )
    (net (code "26") (name "Net-(LED3-K)") (class "Default")
      (node (ref "LED3") (pin "2") (pinfunction "K_2") (pintype "passive"))
      (node (ref "R7") (pin "2") (pinfunction "2_2") (pintype "passive"))
    )
    (net (code "27") (name "Net-(LED4-K)") (class "Default")
      (node (ref "LED4") (pin "2") (pinfunction "K_2") (pintype "passive"))
      (node (ref "R8") (pin "2") (pinfunction "2_2") (pintype "passive"))
    )
    (net (code "28") (name "Net-(Q1-D)") (class "Default")
      (node (ref "Q1") (pin "3") (pinfunction "D_3") (pintype "passive"))
      (node (ref "U1") (pin "COM") (pinfunction "COM_COM") (pintype "passive"))
    )
    (net (code "29") (name "Net-(Q2-D)") (class "Default")
      (node (ref "Q2") (pin "3") (pinfunction "D_3") (pintype "passive"))
      (node (ref "U2") (pin "14") (pinfunction "COM2_14") (pintype "passive"))
    )
    (net (code "30") (name "Net-(Q3-D)") (class "Default")
      (node (ref "Q3") (pin "3") (pinfunction "D_3") (pintype "passive"))
      (node (ref "U2") (pin "13") (pinfunction "COM1_13") (pintype "passive"))
    )
    (net (code "31") (name "Net-(U1-A)") (class "Default")
      (node (ref "R9") (pin "1") (pinfunction "1_1") (pintype "passive"))
      (node (ref "U1") (pin "7") (pinfunction "A_7") (pintype "passive"))
    )
    (net (code "32") (name "Net-(U1-B)") (class "Default")
      (node (ref "R10") (pin "1") (pinfunction "1_1") (pintype "passive"))
      (node (ref "U1") (pin "6") (pinfunction "B_6") (pintype "passive"))
    )
    (net (code "33") (name "Net-(U1-C)") (class "Default")
      (node (ref "R11") (pin "1") (pinfunction "1_1") (pintype "passive"))
      (node (ref "U1") (pin "4") (pinfunction "C_4") (pintype "passive"))
    )
    (net (code "34") (name "Net-(U1-D)") (class "Default")
      (node (ref "R12") (pin "1") (pinfunction "1_1") (pintype "passive"))
      (node (ref "U1") (pin "2") (pinfunction "D_2") (pintype "passive"))
    )
    (net (code "35") (name "Net-(U1-E)") (class "Default")
      (node (ref "R13") (pin "1") (pinfunction "1_1") (pintype "passive"))
      (node (ref "U1") (pin "1") (pinfunction "E_1") (pintype "passive"))
    )
    (net (code "36") (name "Net-(U1-F)") (class "Default")
      (node (ref "R14") (pin "1") (pinfunction "1_1") (pintype "passive"))
      (node (ref "U1") (pin "9") (pinfunction "F_9") (pintype "passive"))
    )
    (net (code "37") (name "Net-(U1-G)") (class "Default")
      (node (ref "R15") (pin "1") (pinfunction "1_1") (pintype "passive"))
      (node (ref "U1") (pin "10") (pinfunction "G_10") (pintype "passive"))
    )
    (net (code "38") (name "Net-(U2-A1)") (class "Default")
      (node (ref "R16") (pin "1") (pinfunction "1_1") (pintype "passive"))
      (node (ref "U2") (pin "16") (pinfunction "A1_16") (pintype "passive"))
    )
    (net (code "39") (name "Net-(U2-A2)") (class "Default")
      (node (ref "R17") (pin "1") (pinfunction "1_1") (pintype "passive"))
      (node (ref "U2") (pin "11") (pinfunction "A2_11") (pintype "passive"))
    )
    (net (code "40") (name "Net-(U2-B1)") (class "Default")
      (node (ref "R18") (pin "1") (pinfunction "1_1") (pintype "passive"))
      (node (ref "U2") (pin "15") (pinfunction "B1_15") (pintype "passive"))
    )
    (net (code "41") (name "Net-(U2-B2)") (class "Default")
      (node (ref "R19") (pin "1") (pinfunction "1_1") (pintype "passive"))
      (node (ref "U2") (pin "10") (pinfunction "B2_10") (pintype "passive"))
    )
    (net (code "42") (name "Net-(U2-C1)") (class "Default")
      (node (ref "R20") (pin "1") (pinfunction "1_1") (pintype "passive"))
      (node (ref "U2") (pin "3") (pinfunction "C1_3") (pintype "passive"))
    )
    (net (code "43") (name "Net-(U2-C2)") (class "Default")
      (node (ref "R21") (pin "1") (pinfunction "1_1") (pintype "passive"))
      (node (ref "U2") (pin "8") (pinfunction "C2_8") (pintype "passive"))
    )
    (net (code "44") (name "Net-(U2-D1)") (class "Default")
      (node (ref "R22") (pin "1") (pinfunction "1_1") (pintype "passive"))
      (node (ref "U2") (pin "2") (pinfunction "D1_2") (pintype "passive"))
    )
    (net (code "45") (name "Net-(U2-D2)") (class "Default")
      (node (ref "R23") (pin "1") (pinfunction "1_1") (pintype "passive"))
      (node (ref "U2") (pin "6") (pinfunction "D2_6") (pintype "passive"))
    )
    (net (code "46") (name "Net-(U2-E1)") (class "Default")
      (node (ref "R24") (pin "1") (pinfunction "1_1") (pintype "passive"))
      (node (ref "U2") (pin "1") (pinfunction "E1_1") (pintype "passive"))
    )
    (net (code "47") (name "Net-(U2-E2)") (class "Default")
      (node (ref "R29") (pin "1") (pinfunction "1_1") (pintype "passive"))
      (node (ref "U2") (pin "5") (pinfunction "E2_5") (pintype "passive"))
    )
    (net (code "48") (name "Net-(U2-F1)") (class "Default")
      (node (ref "R30") (pin "1") (pinfunction "1_1") (pintype "passive"))
      (node (ref "U2") (pin "18") (pinfunction "F1_18") (pintype "passive"))
    )
    (net (code "49") (name "Net-(U2-F2)") (class "Default")
      (node (ref "R31") (pin "1") (pinfunction "1_1") (pintype "passive"))
      (node (ref "U2") (pin "12") (pinfunction "F2_12") (pintype "passive"))
    )
    (net (code "50") (name "Net-(U2-G1)") (class "Default")
      (node (ref "R32") (pin "1") (pinfunction "1_1") (pintype "passive"))
      (node (ref "U2") (pin "17") (pinfunction "G1_17") (pintype "passive"))
    )
    (net (code "51") (name "Net-(U2-G2)") (class "Default")
      (node (ref "R33") (pin "1") (pinfunction "1_1") (pintype "passive"))
      (node (ref "U2") (pin "7") (pinfunction "G2_7") (pintype "passive"))
    )
    (net (code "52") (name "VCC") (class "Default")
      (node (ref "BO1") (pin "7") (pinfunction "VBUS_7") (pintype "power_in"))
      (node (ref "BO2") (pin "18") (pinfunction "AVCC_18") (pintype "power_in"))
      (node (ref "BO2") (pin "7") (pinfunction "VCC_7") (pintype "power_in"))
      (node (ref "C1") (pin "1") (pinfunction "1_1") (pintype "passive"))
      (node (ref "C2") (pin "1") (pinfunction "1_1") (pintype "passive"))
      (node (ref "SW1") (pin "1") (pinfunction "1_1") (pintype "passive"))
      (node (ref "SW2") (pin "1") (pinfunction "1_1") (pintype "passive"))
      (node (ref "SW3") (pin "1") (pinfunction "1_1") (pintype "passive"))
      (node (ref "SW4") (pin "1") (pinfunction "1_1") (pintype "passive"))
      (node (ref "SW6") (pin "C1") (pinfunction "C1_C1") (pintype "passive"))
      (node (ref "SW6") (pin "C2") (pinfunction "C2_C2") (pintype "passive"))
      (node (ref "TP2") (pin "1") (pinfunction "1_1") (pintype "passive"))
    )
    (net (code "53") (name "unconnected-(BO1-CC1-Pad5)") (class "Default")
      (node (ref "BO1") (pin "5") (pinfunction "CC1_5") (pintype "bidirectional"))
    )
    (net (code "54") (name "unconnected-(BO1-CC2-Pad1)") (class "Default")
      (node (ref "BO1") (pin "1") (pinfunction "CC2_1") (pintype "bidirectional"))
    )
    (net (code "55") (name "unconnected-(BO1-D+-Pad3)") (class "Default")
      (node (ref "BO1") (pin "3") (pinfunction "D+_3") (pintype "bidirectional"))
    )
    (net (code "56") (name "unconnected-(BO1-D--Pad4)") (class "Default")
      (node (ref "BO1") (pin "4") (pinfunction "D-_4") (pintype "bidirectional"))
    )
    (net (code "57") (name "unconnected-(BO1-SBU1-Pad2)") (class "Default")
      (node (ref "BO1") (pin "2") (pinfunction "SBU1_2") (pintype "bidirectional"))
    )
    (net (code "58") (name "unconnected-(BO1-SBU2-Pad6)") (class "Default")
      (node (ref "BO1") (pin "6") (pinfunction "SBU2_6") (pintype "bidirectional"))
    )
    (net (code "59") (name "unconnected-(BO2-AREF-Pad19)") (class "Default")
      (node (ref "BO2") (pin "19") (pinfunction "AREF_19") (pintype "input"))
    )
    (net (code "60") (name "unconnected-(BO2-PB3-Pad15)") (class "Default")
      (node (ref "BO2") (pin "15") (pinfunction "PB3_15") (pintype "bidirectional"))
    )
    (net (code "61") (name "unconnected-(BO2-PB4-Pad16)") (class "Default")
      (node (ref "BO2") (pin "16") (pinfunction "PB4_16") (pintype "bidirectional"))
    )
    (net (code "62") (name "unconnected-(BO2-PB5-Pad17)") (class "Default")
      (node (ref "BO2") (pin "17") (pinfunction "PB5_17") (pintype "bidirectional"))
    )
    (net (code "63") (name "unconnected-(BO2-PC4-Pad25)") (class "Default")
      (node (ref "BO2") (pin "25") (pinfunction "PC4_25") (pintype "bidirectional"))
    )
    (net (code "64") (name "unconnected-(BO2-PC5-Pad26)") (class "Default")
      (node (ref "BO2") (pin "26") (pinfunction "PC5_26") (pintype "bidirectional"))
    )
    (net (code "65") (name "unconnected-(BO2-PC6-Pad1)") (class "Default")
      (node (ref "BO2") (pin "1") (pinfunction "PC6_1") (pintype "bidirectional"))
    )
    (net (code "66") (name "unconnected-(BO2-PD7-Pad11)") (class "Default")
      (node (ref "BO2") (pin "11") (pinfunction "PD7_11") (pintype "bidirectional"))
    )
    (net (code "67") (name "unconnected-(SW1-0-Pad3)") (class "Default")
      (node (ref "SW1") (pin "3") (pinfunction "0_3") (pintype "passive"))
    )
    (net (code "68") (name "unconnected-(SW2-0-Pad3)") (class "Default")
      (node (ref "SW2") (pin "3") (pinfunction "0_3") (pintype "passive"))
    )
    (net (code "69") (name "unconnected-(SW3-0-Pad3)") (class "Default")
      (node (ref "SW3") (pin "3") (pinfunction "0_3") (pintype "passive"))
    )
    (net (code "70") (name "unconnected-(SW4-0-Pad3)") (class "Default")
      (node (ref "SW4") (pin "3") (pinfunction "0_3") (pintype "passive"))
    )
    (net (code "71") (name "unconnected-(U1-DP-Pad5)") (class "Default")
      (node (ref "U1") (pin "5") (pinfunction "DP_5") (pintype "passive"))
    )
    (net (code "72") (name "unconnected-(U2-DP1-Pad4)") (class "Default")
      (node (ref "U2") (pin "4") (pinfunction "DP1_4") (pintype "passive"))
    )
    (net (code "73") (name "unconnected-(U2-DP2-Pad9)") (class "Default")
      (node (ref "U2") (pin "9") (pinfunction "DP2_9") (pintype "passive"))
    )
  )
)
